# esc32.net
KiCad netlist of a schematic drawn in Altium Designer
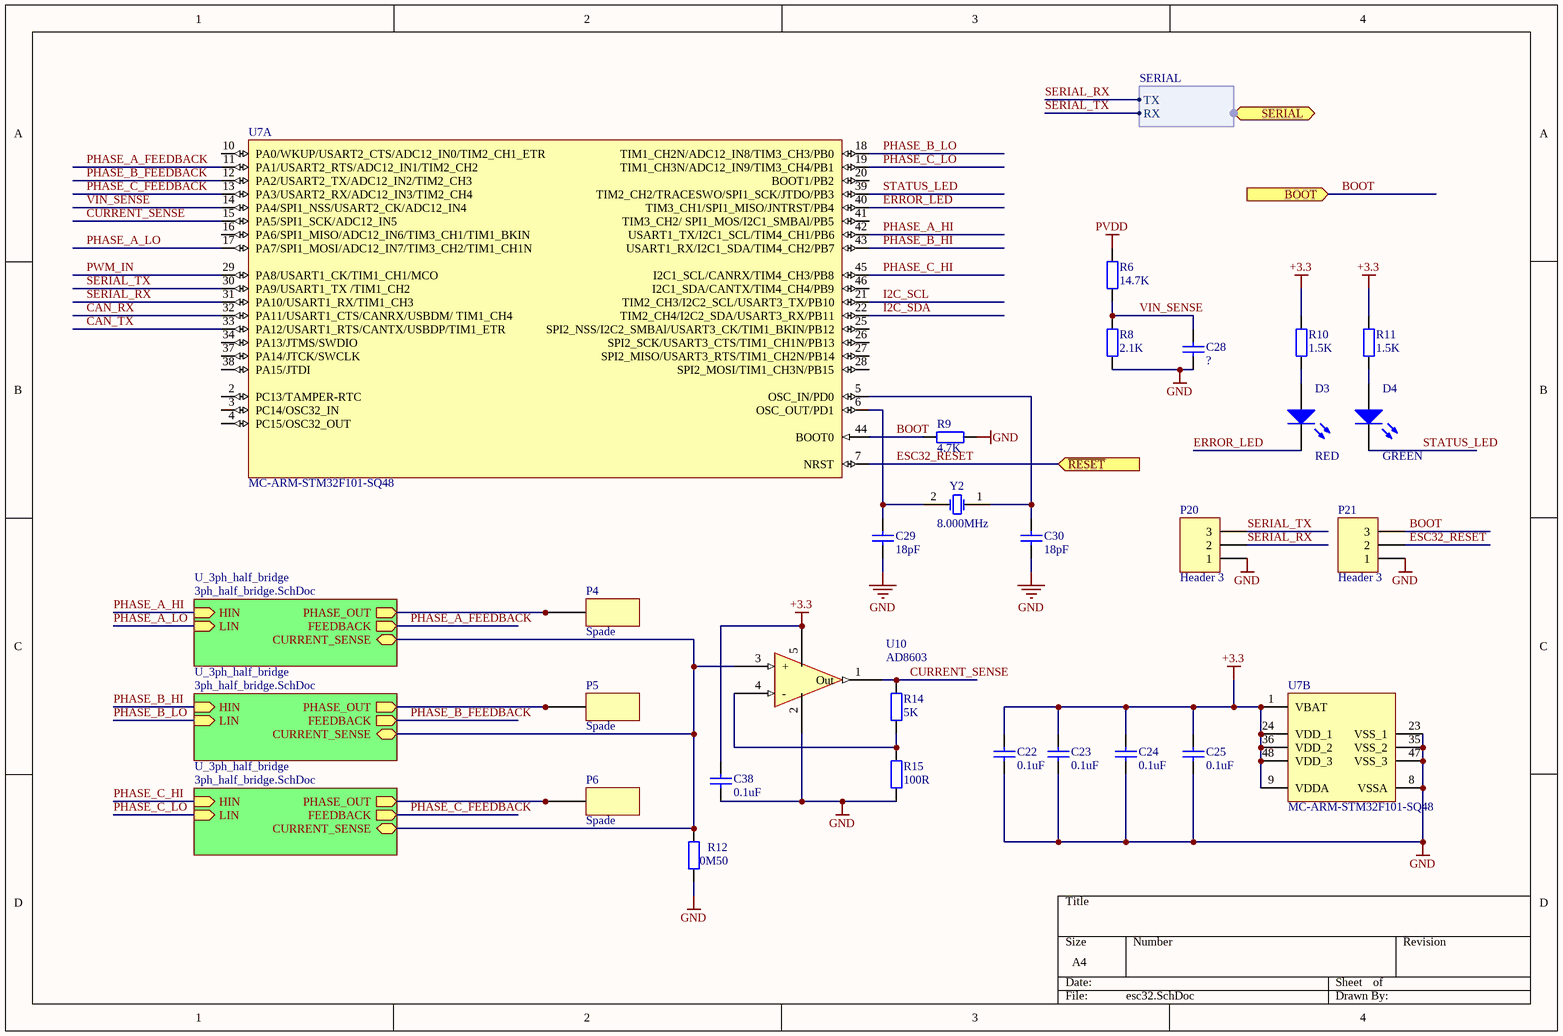
[diagram p0: esc32.SchDoc]

(export (version "E")
  (design (tool "Eeschema 10.0.6"))
  (components
    (comp (ref "C22")
      (value "0.1uF")
      (footprint "C0603")
      (description "Capacitor")
      (fields (field (name "Comment") "Cap"))
      (libsource (lib "Miscellaneous Devices") (part "Cap"))
    )
    (comp (ref "C23")
      (value "0.1uF")
      (footprint "C0603")
      (description "Capacitor")
      (fields (field (name "Comment") "Cap"))
      (libsource (lib "Miscellaneous Devices") (part "Cap"))
    )
    (comp (ref "C24")
      (value "0.1uF")
      (footprint "C0603")
      (description "Capacitor")
      (fields (field (name "Comment") "Cap"))
      (libsource (lib "Miscellaneous Devices") (part "Cap"))
    )
    (comp (ref "C25")
      (value "0.1uF")
      (footprint "C0603")
      (description "Capacitor")
      (fields (field (name "Comment") "Cap"))
      (libsource (lib "Miscellaneous Devices") (part "Cap"))
    )
    (comp (ref "C28")
      (value "?")
      (footprint "C0603")
      (description "Capacitor")
      (fields (field (name "Comment") "Cap"))
      (libsource (lib "Miscellaneous Devices") (part "Cap"))
    )
    (comp (ref "C29")
      (value "18pF")
      (footprint "C0603")
      (description "Capacitor")
      (fields (field (name "Comment") "Cap"))
      (libsource (lib "Miscellaneous Devices") (part "Cap"))
    )
    (comp (ref "C30")
      (value "18pF")
      (footprint "C0603")
      (description "Capacitor")
      (fields (field (name "Comment") "Cap"))
      (libsource (lib "Miscellaneous Devices") (part "Cap"))
    )
    (comp (ref "C38")
      (value "0.1uF")
      (footprint "C0603")
      (description "Capacitor")
      (fields (field (name "Comment") "Cap"))
      (libsource (lib "Miscellaneous Devices") (part "Cap"))
    )
    (comp (ref "D3")
      (value "RED")
      (footprint "LGQ971")
      (description "Typical RED, GREEN, YELLOW, AMBER GaAs LED")
      (libsource (lib "Miscellaneous Devices") (part "LED2"))
    )
    (comp (ref "D4")
      (value "GREEN")
      (footprint "LGQ971")
      (description "Typical RED, GREEN, YELLOW, AMBER GaAs LED")
      (libsource (lib "Miscellaneous Devices") (part "LED2"))
    )
    (comp (ref "P4")
      (value "Spade")
      (footprint "3866A")
      (description "Space connector")
      (libsource (lib "3866A68 (spade connectors)") (part "3866A"))
    )
    (comp (ref "P5")
      (value "Spade")
      (footprint "3866A")
      (description "Space connector")
      (libsource (lib "3866A68 (spade connectors)") (part "3866A"))
    )
    (comp (ref "P6")
      (value "Spade")
      (footprint "3866A")
      (description "Space connector")
      (libsource (lib "3866A68 (spade connectors)") (part "3866A"))
    )
    (comp (ref "P20")
      (value "Header 3")
      (footprint "HDR1X3")
      (description "Header, 3-Pin")
      (fields (field (name "PUBLISHER") "Altium Limited"))
      (libsource (lib "Miscellaneous Connectors") (part "Header 3"))
    )
    (comp (ref "P21")
      (value "Header 3")
      (footprint "HDR1X3")
      (description "Header, 3-Pin")
      (fields (field (name "PUBLISHER") "Altium Limited"))
      (libsource (lib "Miscellaneous Connectors") (part "Header 3"))
    )
    (comp (ref "R6")
      (value "14.7K")
      (footprint "R0603")
      (description "Resistor")
      (fields (field (name "Comment") "Res"))
      (libsource (lib "Miscellaneous Devices") (part "Res2"))
    )
    (comp (ref "R8")
      (value "2.1K")
      (footprint "R0603")
      (description "Resistor")
      (fields (field (name "Comment") "Res"))
      (libsource (lib "Miscellaneous Devices") (part "Res2"))
    )
    (comp (ref "R9")
      (value "4.7K")
      (footprint "R0603")
      (description "Resistor")
      (fields (field (name "Comment") "Res"))
      (libsource (lib "") (part "Res2_1"))
    )
    (comp (ref "R10")
      (value "1.5K")
      (footprint "R0603")
      (description "Resistor")
      (fields (field (name "Comment") "Res"))
      (libsource (lib "Miscellaneous Devices") (part "Res2"))
    )
    (comp (ref "R11")
      (value "1.5K")
      (footprint "R0603")
      (description "Resistor")
      (fields (field (name "Comment") "Res"))
      (libsource (lib "Miscellaneous Devices") (part "Res2"))
    )
    (comp (ref "R12")
      (value "0M50")
      (footprint "TLR3A")
      (description "Resistor")
      (fields (field (name "Comment") "Res"))
      (libsource (lib "") (part "Res2_2"))
    )
    (comp (ref "R14")
      (value "5K")
      (footprint "R0603")
      (description "Resistor")
      (fields (field (name "Comment") "Res"))
      (libsource (lib "Miscellaneous Devices") (part "Res2"))
    )
    (comp (ref "R15")
      (value "100R")
      (footprint "R0603")
      (description "Resistor")
      (fields (field (name "Comment") "Res"))
      (libsource (lib "Miscellaneous Devices") (part "Res2"))
    )
    (comp (ref "U7")
      (value "MC-ARM-STM32F101-SQ48")
      (footprint "LQFP48_L")
      (libsource (lib "MC-ARM-STM32F101-SQ48") (part "MC-ARM-STM32F101-SQ48"))
    )
    (comp (ref "U10")
      (value "AD8603")
      (footprint "SOT95P255X100-5N")
      (description "Precision op-amp")
      (libsource (lib "AD8603") (part "AD8603"))
    )
    (comp (ref "Y2")
      (value "8.000MHz")
      (footprint "C3E-24.000-12-3030-X")
      (description "Crystal Oscillator")
      (fields (field (name "Comment") "XTAL"))
      (libsource (lib "Miscellaneous Devices") (part "XTAL"))
    )
  )
  (nets
    (net (code "2") (name "+3.3") (class "Default")
      (node (ref "C22") (pin "1") (pinfunction "1_1") (pintype "passive"))
      (node (ref "C23") (pin "1") (pinfunction "1_1") (pintype "passive"))
      (node (ref "C24") (pin "1") (pinfunction "1_1") (pintype "passive"))
      (node (ref "C25") (pin "1") (pinfunction "1_1") (pintype "passive"))
      (node (ref "C38") (pin "1") (pinfunction "1_1") (pintype "passive"))
      (node (ref "R10") (pin "2") (pinfunction "2_2") (pintype "passive"))
      (node (ref "R11") (pin "2") (pinfunction "2_2") (pintype "passive"))
      (node (ref "U10") (pin "5") (pinfunction "V+_5") (pintype "power_in"))
      (node (ref "U7") (pin "1") (pinfunction "VBAT_1") (pintype "power_in"))
      (node (ref "U7") (pin "24") (pinfunction "VDD_1_24") (pintype "power_in"))
      (node (ref "U7") (pin "36") (pinfunction "VDD_2_36") (pintype "power_in"))
      (node (ref "U7") (pin "48") (pinfunction "VDD_3_48") (pintype "power_in"))
      (node (ref "U7") (pin "9") (pinfunction "VDDA_9") (pintype "power_in"))
    )
    (net (code "3") (name "/BOOT") (class "Default")
      (node (ref "P21") (pin "3") (pinfunction "3_3") (pintype "passive"))
      (node (ref "R9") (pin "2") (pinfunction "2_2") (pintype "passive"))
      (node (ref "U7") (pin "44") (pinfunction "BOOT0_44") (pintype "input"))
    )
    (net (code "4") (name "/CAN_RX") (class "Default")
      (node (ref "U7") (pin "32") (pinfunction "PA11/USART1_CTS/CANRX/USBDM/_TIM1_CH4_32") (pintype "bidirectional"))
    )
    (net (code "5") (name "/CAN_TX") (class "Default")
      (node (ref "U7") (pin "33") (pinfunction "PA12/USART1_RTS/CANTX/USBDP/TIM1_ETR_33") (pintype "bidirectional"))
    )
    (net (code "6") (name "/CURRENT_SENSE") (class "Default")
      (node (ref "R14") (pin "2") (pinfunction "2_2") (pintype "passive"))
      (node (ref "U10") (pin "1") (pinfunction "Out_1") (pintype "output"))
      (node (ref "U7") (pin "15") (pinfunction "PA5/SPI1_SCK/ADC12_IN5_15") (pintype "bidirectional"))
    )
    (net (code "7") (name "/CURRENT_SENSE_1") (class "Default")
      (node (ref "R12") (pin "1") (pinfunction "1_1") (pintype "passive"))
      (node (ref "U10") (pin "3") (pinfunction "+_3") (pintype "input"))
    )
    (net (code "8") (name "/ERROR_LED") (class "Default")
      (node (ref "D3") (pin "2") (pinfunction "K_2") (pintype "passive"))
      (node (ref "U7") (pin "40") (pinfunction "TIM3_CH1/SPI1_MISO/JNTRST/PB4_40") (pintype "bidirectional"))
    )
    (net (code "9") (name "/ESC32_RESET") (class "Default")
      (node (ref "P21") (pin "2") (pinfunction "2_2") (pintype "passive"))
      (node (ref "U7") (pin "7") (pinfunction "NRST_7") (pintype "bidirectional"))
    )
    (net (code "10") (name "/I2C_SCL") (class "Default")
      (node (ref "U7") (pin "21") (pinfunction "TIM2_CH3/I2C2_SCL/USART3_TX/PB10_21") (pintype "bidirectional"))
    )
    (net (code "11") (name "/I2C_SDA") (class "Default")
      (node (ref "U7") (pin "22") (pinfunction "TIM2_CH4/I2C2_SDA/USART3_RX/PB11_22") (pintype "bidirectional"))
    )
    (net (code "12") (name "/PHASE_A_FEEDBACK") (class "Default")
      (node (ref "U7") (pin "11") (pinfunction "PA1/USART2_RTS/ADC12_IN1/TIM2_CH2_11") (pintype "bidirectional"))
    )
    (net (code "13") (name "/PHASE_A_HI") (class "Default")
      (node (ref "U7") (pin "42") (pinfunction "USART1_TX/I2C1_SCL/TIM4_CH1/PB6_42") (pintype "bidirectional"))
    )
    (net (code "14") (name "/PHASE_A_LO") (class "Default")
      (node (ref "U7") (pin "17") (pinfunction "PA7/SPI1_MOSI/ADC12_IN7/TIM3_CH2/TIM1_CH1N_17") (pintype "bidirectional"))
    )
    (net (code "15") (name "/PHASE_B_FEEDBACK") (class "Default")
      (node (ref "U7") (pin "12") (pinfunction "PA2/USART2_TX/ADC12_IN2/TIM2_CH3_12") (pintype "bidirectional"))
    )
    (net (code "16") (name "/PHASE_B_HI") (class "Default")
      (node (ref "U7") (pin "43") (pinfunction "USART1_RX/I2C1_SDA/TIM4_CH2/PB7_43") (pintype "bidirectional"))
    )
    (net (code "17") (name "/PHASE_B_LO") (class "Default")
      (node (ref "U7") (pin "18") (pinfunction "TIM1_CH2N/ADC12_IN8/TIM3_CH3/PB0_18") (pintype "bidirectional"))
    )
    (net (code "18") (name "/PHASE_C_FEEDBACK") (class "Default")
      (node (ref "U7") (pin "13") (pinfunction "PA3/USART2_RX/ADC12_IN3/TIM2_CH4_13") (pintype "bidirectional"))
    )
    (net (code "19") (name "/PHASE_C_HI") (class "Default")
      (node (ref "U7") (pin "45") (pinfunction "I2C1_SCL/CANRX/TIM4_CH3/PB8_45") (pintype "bidirectional"))
    )
    (net (code "20") (name "/PHASE_C_LO") (class "Default")
      (node (ref "U7") (pin "19") (pinfunction "TIM1_CH3N/ADC12_IN9/TIM3_CH4/PB1_19") (pintype "bidirectional"))
    )
    (net (code "21") (name "/PHASE_OUT") (class "Default")
      (node (ref "P4") (pin "1") (pinfunction "33_1") (pintype "passive"))
      (node (ref "P4") (pin "2") (pinfunction "32_2") (pintype "passive"))
    )
    (net (code "22") (name "/PHASE_OUT_1") (class "Default")
      (node (ref "P6") (pin "1") (pinfunction "33_1") (pintype "passive"))
      (node (ref "P6") (pin "2") (pinfunction "32_2") (pintype "passive"))
    )
    (net (code "23") (name "/PHASE_OUT_2") (class "Default")
      (node (ref "P5") (pin "1") (pinfunction "33_1") (pintype "passive"))
      (node (ref "P5") (pin "2") (pinfunction "32_2") (pintype "passive"))
    )
    (net (code "24") (name "/PWM_IN") (class "Default")
      (node (ref "U7") (pin "29") (pinfunction "PA8/USART1_CK/TIM1_CH1/MCO_29") (pintype "bidirectional"))
    )
    (net (code "25") (name "/SERIAL_RX") (class "Default")
      (node (ref "P20") (pin "2") (pinfunction "2_2") (pintype "passive"))
      (node (ref "U7") (pin "31") (pinfunction "PA10/USART1_RX/TIM1_CH3_31") (pintype "bidirectional"))
    )
    (net (code "26") (name "/SERIAL_TX") (class "Default")
      (node (ref "P20") (pin "3") (pinfunction "3_3") (pintype "passive"))
      (node (ref "U7") (pin "30") (pinfunction "PA9/USART1_TX_/TIM1_CH2_30") (pintype "bidirectional"))
    )
    (net (code "27") (name "/STATUS_LED") (class "Default")
      (node (ref "D4") (pin "2") (pinfunction "K_2") (pintype "passive"))
      (node (ref "U7") (pin "39") (pinfunction "TIM2_CH2/TRACESWO/SPI1_SCK/JTDO/PB3_39") (pintype "bidirectional"))
    )
    (net (code "28") (name "/VIN_SENSE") (class "Default")
      (node (ref "C28") (pin "1") (pinfunction "1_1") (pintype "passive"))
      (node (ref "R6") (pin "1") (pinfunction "1_1") (pintype "passive"))
      (node (ref "R8") (pin "2") (pinfunction "2_2") (pintype "passive"))
      (node (ref "U7") (pin "14") (pinfunction "PA4/SPI1_NSS/USART2_CK/ADC12_IN4_14") (pintype "bidirectional"))
    )
    (net (code "30") (name "GND") (class "Default")
      (node (ref "C22") (pin "2") (pinfunction "2_2") (pintype "passive"))
      (node (ref "C23") (pin "2") (pinfunction "2_2") (pintype "passive"))
      (node (ref "C24") (pin "2") (pinfunction "2_2") (pintype "passive"))
      (node (ref "C25") (pin "2") (pinfunction "2_2") (pintype "passive"))
      (node (ref "C28") (pin "2") (pinfunction "2_2") (pintype "passive"))
      (node (ref "C29") (pin "2") (pinfunction "2_2") (pintype "passive"))
      (node (ref "C30") (pin "2") (pinfunction "2_2") (pintype "passive"))
      (node (ref "C38") (pin "2") (pinfunction "2_2") (pintype "passive"))
      (node (ref "P20") (pin "1") (pinfunction "1_1") (pintype "passive"))
      (node (ref "P21") (pin "1") (pinfunction "1_1") (pintype "passive"))
      (node (ref "R12") (pin "2") (pinfunction "2_2") (pintype "passive"))
      (node (ref "R15") (pin "1") (pinfunction "1_1") (pintype "passive"))
      (node (ref "R8") (pin "1") (pinfunction "1_1") (pintype "passive"))
      (node (ref "R9") (pin "1") (pinfunction "1_1") (pintype "passive"))
      (node (ref "U10") (pin "2") (pinfunction "V-_2") (pintype "power_in"))
      (node (ref "U7") (pin "23") (pinfunction "VSS_1_23") (pintype "power_in"))
      (node (ref "U7") (pin "35") (pinfunction "VSS_2_35") (pintype "power_in"))
      (node (ref "U7") (pin "47") (pinfunction "VSS_3_47") (pintype "power_in"))
      (node (ref "U7") (pin "8") (pinfunction "VSSA_8") (pintype "power_in"))
    )
    (net (code "31") (name "Net-(D3-A)") (class "Default")
      (node (ref "D3") (pin "1") (pinfunction "A_1") (pintype "passive"))
      (node (ref "R10") (pin "1") (pinfunction "1_1") (pintype "passive"))
    )
    (net (code "32") (name "Net-(D4-A)") (class "Default")
      (node (ref "D4") (pin "1") (pinfunction "A_1") (pintype "passive"))
      (node (ref "R11") (pin "1") (pinfunction "1_1") (pintype "passive"))
    )
    (net (code "33") (name "Net-(U7A-OSC_IN{slash}PD0)") (class "Default")
      (node (ref "C30") (pin "1") (pinfunction "1_1") (pintype "passive"))
      (node (ref "U7") (pin "5") (pinfunction "OSC_IN/PD0_5") (pintype "bidirectional"))
      (node (ref "Y2") (pin "1") (pinfunction "OSC1_1") (pintype "passive"))
    )
    (net (code "34") (name "Net-(U7A-OSC_OUT{slash}PD1)") (class "Default")
      (node (ref "C29") (pin "1") (pinfunction "1_1") (pintype "passive"))
      (node (ref "U7") (pin "6") (pinfunction "OSC_OUT/PD1_6") (pintype "bidirectional"))
      (node (ref "Y2") (pin "2") (pinfunction "OSC2_2") (pintype "passive"))
    )
    (net (code "35") (name "Net-(U10--)") (class "Default")
      (node (ref "R14") (pin "1") (pinfunction "1_1") (pintype "passive"))
      (node (ref "R15") (pin "2") (pinfunction "2_2") (pintype "passive"))
      (node (ref "U10") (pin "4") (pinfunction "-_4") (pintype "input"))
    )
    (net (code "36") (name "PVDD") (class "Default")
      (node (ref "R6") (pin "2") (pinfunction "2_2") (pintype "passive"))
    )
    (net (code "37") (name "unconnected-(U7A-BOOT1{slash}PB2-Pad20)") (class "Default")
      (node (ref "U7") (pin "20") (pinfunction "BOOT1/PB2_20") (pintype "bidirectional"))
    )
    (net (code "38") (name "unconnected-(U7A-I2C1_SDA{slash}CANTX{slash}TIM4_CH4{slash}PB9-Pad46)") (class "Default")
      (node (ref "U7") (pin "46") (pinfunction "I2C1_SDA/CANTX/TIM4_CH4/PB9_46") (pintype "bidirectional"))
    )
    (net (code "39") (name "unconnected-(U7A-PA0{slash}WKUP{slash}USART2_CTS{slash}ADC12_IN0{slash}TIM2_CH1_ETR-Pad10)") (class "Default")
      (node (ref "U7") (pin "10") (pinfunction "PA0/WKUP/USART2_CTS/ADC12_IN0/TIM2_CH1_ETR_10") (pintype "bidirectional"))
    )
    (net (code "40") (name "unconnected-(U7A-PA6{slash}SPI1_MISO{slash}ADC12_IN6{slash}TIM3_CH1{slash}TIM1_BKIN-Pad16)") (class "Default")
      (node (ref "U7") (pin "16") (pinfunction "PA6/SPI1_MISO/ADC12_IN6/TIM3_CH1/TIM1_BKIN_16") (pintype "bidirectional"))
    )
    (net (code "41") (name "unconnected-(U7A-PA13{slash}JTMS{slash}SWDIO-Pad34)") (class "Default")
      (node (ref "U7") (pin "34") (pinfunction "PA13/JTMS/SWDIO_34") (pintype "bidirectional"))
    )
    (net (code "42") (name "unconnected-(U7A-PA14{slash}JTCK{slash}SWCLK-Pad37)") (class "Default")
      (node (ref "U7") (pin "37") (pinfunction "PA14/JTCK/SWCLK_37") (pintype "bidirectional"))
    )
    (net (code "43") (name "unconnected-(U7A-PA15{slash}JTDI-Pad38)") (class "Default")
      (node (ref "U7") (pin "38") (pinfunction "PA15/JTDI_38") (pintype "bidirectional"))
    )
    (net (code "44") (name "unconnected-(U7A-PC13{slash}TAMPER-RTC-Pad2)") (class "Default")
      (node (ref "U7") (pin "2") (pinfunction "PC13/TAMPER-RTC_2") (pintype "bidirectional"))
    )
    (net (code "45") (name "unconnected-(U7A-PC14{slash}OSC32_IN-Pad3)") (class "Default")
      (node (ref "U7") (pin "3") (pinfunction "PC14/OSC32_IN_3") (pintype "bidirectional"))
    )
    (net (code "46") (name "unconnected-(U7A-PC15{slash}OSC32_OUT-Pad4)") (class "Default")
      (node (ref "U7") (pin "4") (pinfunction "PC15/OSC32_OUT_4") (pintype "bidirectional"))
    )
    (net (code "47") (name "unconnected-(U7A-SPI2_MISO{slash}USART3_RTS{slash}TIM1_CH2N{slash}PB14-Pad27)") (class "Default")
      (node (ref "U7") (pin "27") (pinfunction "SPI2_MISO/USART3_RTS/TIM1_CH2N/PB14_27") (pintype "bidirectional"))
    )
    (net (code "48") (name "unconnected-(U7A-SPI2_MOSI{slash}TIM1_CH3N{slash}PB15-Pad28)") (class "Default")
      (node (ref "U7") (pin "28") (pinfunction "SPI2_MOSI/TIM1_CH3N/PB15_28") (pintype "bidirectional"))
    )
    (net (code "49") (name "unconnected-(U7A-SPI2_NSS{slash}I2C2_SMBAl{slash}USART3_CK{slash}TIM1_BKIN{slash}PB12-Pad25)") (class "Default")
      (node (ref "U7") (pin "25") (pinfunction "SPI2_NSS/I2C2_SMBAl/USART3_CK/TIM1_BKIN/PB12_25") (pintype "bidirectional"))
    )
    (net (code "50") (name "unconnected-(U7A-SPI2_SCK{slash}USART3_CTS{slash}TIM1_CH1N{slash}PB13-Pad26)") (class "Default")
      (node (ref "U7") (pin "26") (pinfunction "SPI2_SCK/USART3_CTS/TIM1_CH1N/PB13_26") (pintype "bidirectional"))
    )
    (net (code "51") (name "unconnected-(U7A-TIM3_CH2{slash}_SPI1_MOS{slash}I2C1_SMBAl{slash}PB5-Pad41)") (class "Default")
      (node (ref "U7") (pin "41") (pinfunction "TIM3_CH2/_SPI1_MOS/I2C1_SMBAl/PB5_41") (pintype "bidirectional"))
    )
  )
)
